# ADC_PCM1802.net
KiCad netlist of a schematic drawn in Altium Designer
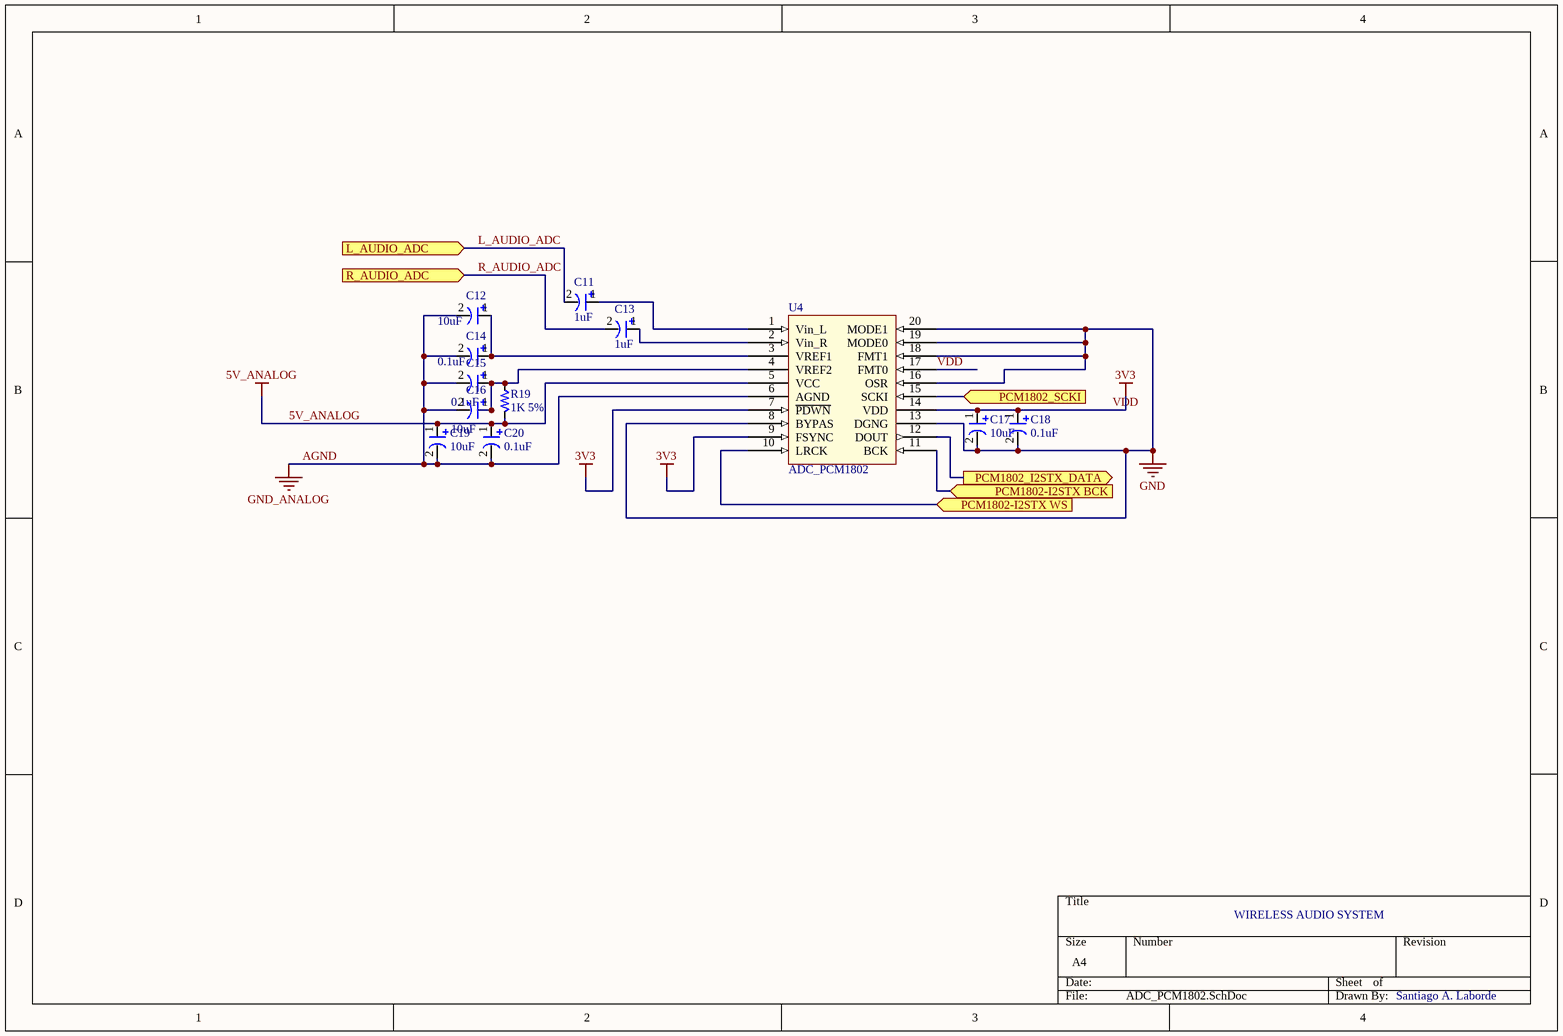
[diagram p0: ADC_PCM1802.SchDoc]

(export (version "E")
  (design (tool "Eeschema 10.0.6"))
  (components
    (comp (ref "C11")
      (value "1uF")
      (footprint "RAD-0.1")
      (description "Polarysed Capacitor")
      (libsource (lib "TD2_Project") (part "Capacitor_Pol"))
    )
    (comp (ref "C12")
      (value "10uF")
      (footprint "14-1210")
      (description "Polarysed Capacitor")
      (libsource (lib "TD2_Project") (part "Capacitor_Pol"))
    )
    (comp (ref "C13")
      (value "1uF")
      (footprint "RAD-0.1")
      (description "Polarysed Capacitor")
      (libsource (lib "TD2_Project") (part "Capacitor_Pol"))
    )
    (comp (ref "C14")
      (value "0.1uF")
      (footprint "C_0805_Pol")
      (description "Polarysed Capacitor")
      (libsource (lib "TD2_Project") (part "Capacitor_Pol"))
    )
    (comp (ref "C15")
      (value "0.1uF")
      (footprint "C_0805_Pol")
      (description "Polarysed Capacitor")
      (libsource (lib "TD2_Project") (part "Capacitor_Pol"))
    )
    (comp (ref "C16")
      (value "10uF")
      (footprint "14-1210")
      (description "Polarysed Capacitor")
      (libsource (lib "TD2_Project") (part "Capacitor_Pol"))
    )
    (comp (ref "C17")
      (value "10uF")
      (footprint "14-1210")
      (description "Polarysed Capacitor")
      (libsource (lib "TD2_Project") (part "Capacitor_Pol"))
    )
    (comp (ref "C18")
      (value "0.1uF")
      (footprint "C_0805_Pol")
      (description "Polarysed Capacitor")
      (libsource (lib "TD2_Project") (part "Capacitor_Pol"))
    )
    (comp (ref "C19")
      (value "10uF")
      (footprint "14-1210")
      (description "Polarysed Capacitor")
      (libsource (lib "TD2_Project") (part "Capacitor_Pol"))
    )
    (comp (ref "C20")
      (value "0.1uF")
      (footprint "C_0805_Pol")
      (description "Polarysed Capacitor")
      (libsource (lib "TD2_Project") (part "Capacitor_Pol"))
    )
    (comp (ref "R19") (value "1K 5%") (footprint "R_0805") (libsource (lib "TD2_Project") (part "Resistor")))
    (comp (ref "U4")
      (value "ADC_PCM1802")
      (footprint "SSOP (20)")
      (libsource (lib "TD2_Project") (part "ADC_PCM1802"))
    )
  )
  (nets
    (net (code "1") (name "/L_AUDIO_ADC") (class "Default") (node (ref "C11") (pin "2") (pintype "passive")))
    (net (code "2") (name "/PCM1802-I2STX BCK") (class "Default")
      (node (ref "U4") (pin "11") (pinfunction "BCK_11") (pintype "input"))
    )
    (net (code "3") (name "/PCM1802-I2STX WS") (class "Default")
      (node (ref "U4") (pin "10") (pinfunction "LRCK_10") (pintype "input"))
    )
    (net (code "4") (name "/PCM1802_I2STX_DATA") (class "Default")
      (node (ref "U4") (pin "12") (pinfunction "DOUT_12") (pintype "output"))
    )
    (net (code "5") (name "/PCM1802_SCKI") (class "Default")
      (node (ref "U4") (pin "15") (pinfunction "SCKI_15") (pintype "input"))
    )
    (net (code "6") (name "/R_AUDIO_ADC") (class "Default") (node (ref "C13") (pin "2") (pintype "passive")))
    (net (code "7") (name "3V3") (class "Default")
      (node (ref "C17") (pin "1") (pintype "passive"))
      (node (ref "C18") (pin "1") (pintype "passive"))
      (node (ref "U4") (pin "14") (pinfunction "VDD_14") (pintype "passive"))
      (node (ref "U4") (pin "17") (pinfunction "FMT0_17") (pintype "input"))
      (node (ref "U4") (pin "7") (pinfunction "~{PDWN}_7") (pintype "input"))
      (node (ref "U4") (pin "9") (pinfunction "FSYNC_9") (pintype "input"))
    )
    (net (code "8") (name "5V_ANALOG") (class "Default")
      (node (ref "C19") (pin "1") (pintype "passive"))
      (node (ref "C20") (pin "1") (pintype "passive"))
      (node (ref "R19") (pin "1") (pinfunction "1_1") (pintype "passive"))
      (node (ref "U4") (pin "5") (pinfunction "VCC_5") (pintype "passive"))
    )
    (net (code "9") (name "GND") (class "Default")
      (node (ref "C17") (pin "2") (pintype "passive"))
      (node (ref "C18") (pin "2") (pintype "passive"))
      (node (ref "U4") (pin "13") (pinfunction "DGNG_13") (pintype "passive"))
      (node (ref "U4") (pin "16") (pinfunction "OSR_16") (pintype "input"))
      (node (ref "U4") (pin "18") (pinfunction "FMT1_18") (pintype "input"))
      (node (ref "U4") (pin "19") (pinfunction "MODE0_19") (pintype "input"))
      (node (ref "U4") (pin "20") (pinfunction "MODE1_20") (pintype "input"))
      (node (ref "U4") (pin "8") (pinfunction "BYPAS_8") (pintype "input"))
    )
    (net (code "10") (name "GND_ANALOG") (class "Default")
      (node (ref "C12") (pin "2") (pintype "passive"))
      (node (ref "C14") (pin "2") (pintype "passive"))
      (node (ref "C15") (pin "2") (pintype "passive"))
      (node (ref "C16") (pin "2") (pintype "passive"))
      (node (ref "C19") (pin "2") (pintype "passive"))
      (node (ref "C20") (pin "2") (pintype "passive"))
      (node (ref "U4") (pin "6") (pinfunction "AGND_6") (pintype "passive"))
    )
    (net (code "11") (name "Net-(U4-VREF1)") (class "Default")
      (node (ref "C12") (pin "1") (pintype "passive"))
      (node (ref "C14") (pin "1") (pintype "passive"))
      (node (ref "U4") (pin "3") (pinfunction "VREF1_3") (pintype "passive"))
    )
    (net (code "12") (name "Net-(U4-VREF2)") (class "Default")
      (node (ref "C15") (pin "1") (pintype "passive"))
      (node (ref "C16") (pin "1") (pintype "passive"))
      (node (ref "R19") (pin "2") (pinfunction "2_2") (pintype "passive"))
      (node (ref "U4") (pin "4") (pinfunction "VREF2_4") (pintype "passive"))
    )
    (net (code "13") (name "Net-(U4-Vin_L)") (class "Default")
      (node (ref "C11") (pin "1") (pintype "passive"))
      (node (ref "U4") (pin "1") (pinfunction "Vin_L_1") (pintype "input"))
    )
    (net (code "14") (name "Net-(U4-Vin_R)") (class "Default")
      (node (ref "C13") (pin "1") (pintype "passive"))
      (node (ref "U4") (pin "2") (pinfunction "Vin_R_2") (pintype "input"))
    )
  )
)
